# Conectors.net
KiCad netlist of a schematic drawn in Altium Designer
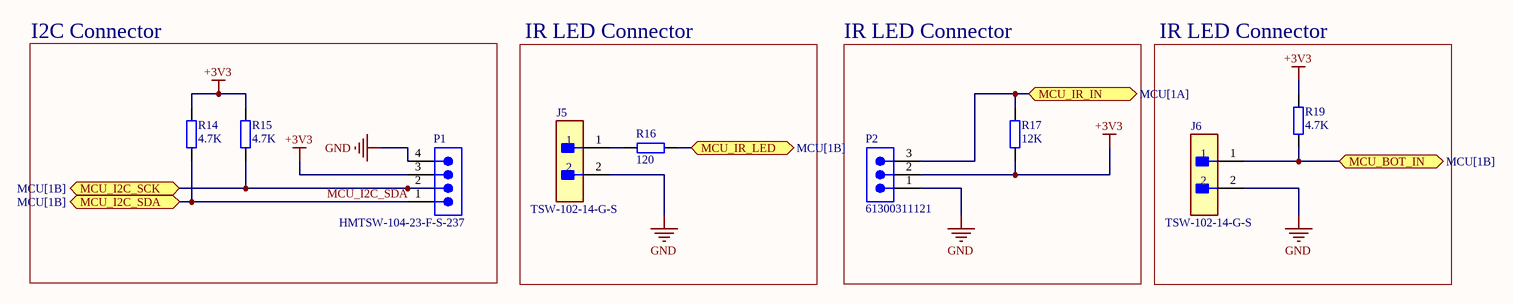
[diagram p0: Conectors.SchDoc]

(export (version "E")
  (design (tool "Eeschema 10.0.6"))
  (components
    (comp (ref "J5")
      (value "TSW-102-14-G-S")
      (footprint "FP-TSW-102-14-G-S-MFG")
      (description "CONN HEADER VERT 2POS 2.54MM")
      (libsource (lib "Altium Content Vault") (part "88c1139f9d239099ffebecbe3f7647a"))
    )
    (comp (ref "J6")
      (value "TSW-102-14-G-S")
      (footprint "FP-TSW-102-14-G-S-MFG")
      (description "CONN HEADER VERT 2POS 2.54MM")
      (libsource (lib "Altium Content Vault") (part "88c1139f9d239099ffebecbe3f7647a"))
    )
    (comp (ref "P1")
      (value "HMTSW-104-23-F-S-237")
      (footprint "SMTC-HMTSW-104-23-X-S-237")
      (fields (field (name "MANUFACTURER") "Samtec"))
      (libsource (lib "Altium Content Vault") (part "SMTC-HMTSW-104-23-X-S-237"))
    )
    (comp (ref "P2")
      (value "61300311121")
      (footprint "61300311121")
      (libsource (lib "Altium Content Vault") (part "Header_Male_1R_03P"))
    )
    (comp (ref "R14")
      (value "4.7K")
      (footprint "RES_0603")
      (description "Resistor SMD 0603")
      (libsource (lib "Schematic-Lib-PhilsLab") (part "RES_0603"))
    )
    (comp (ref "R15")
      (value "4.7K")
      (footprint "RES_0603")
      (description "Resistor SMD 0603")
      (libsource (lib "Schematic-Lib-PhilsLab") (part "RES_0603"))
    )
    (comp (ref "R16")
      (value "120")
      (footprint "RES_0603")
      (description "Resistor SMD 0603")
      (libsource (lib "Schematic-Lib-PhilsLab") (part "RES_0603"))
    )
    (comp (ref "R17")
      (value "12K")
      (footprint "RES_0603")
      (description "Resistor SMD 0603")
      (libsource (lib "Schematic-Lib-PhilsLab") (part "RES_0603"))
    )
    (comp (ref "R19")
      (value "4.7K")
      (footprint "RES_0603")
      (description "Resistor SMD 0603")
      (libsource (lib "Schematic-Lib-PhilsLab") (part "RES_0603"))
    )
  )
  (nets
    (net (code "1") (name "+3V3") (class "Default")
      (node (ref "P1") (pin "3") (pinfunction "3_3") (pintype "passive"))
      (node (ref "P2") (pin "2") (pinfunction "2_2") (pintype "passive"))
      (node (ref "R14") (pin "2") (pinfunction "2_2") (pintype "passive"))
      (node (ref "R15") (pin "2") (pinfunction "2_2") (pintype "passive"))
      (node (ref "R17") (pin "1") (pinfunction "1_1") (pintype "passive"))
      (node (ref "R19") (pin "1") (pinfunction "1_1") (pintype "passive"))
    )
    (net (code "2") (name "/MCU_BOT_IN") (class "Default")
      (node (ref "J6") (pin "1") (pinfunction "1_1") (pintype "passive"))
      (node (ref "R19") (pin "2") (pinfunction "2_2") (pintype "passive"))
    )
    (net (code "3") (name "/MCU_I2C_SCK") (class "Default")
      (node (ref "P1") (pin "2") (pinfunction "2_2") (pintype "passive"))
      (node (ref "R15") (pin "1") (pinfunction "1_1") (pintype "passive"))
    )
    (net (code "4") (name "/MCU_I2C_SDA") (class "Default")
      (node (ref "P1") (pin "1") (pinfunction "1_1") (pintype "passive"))
      (node (ref "R14") (pin "1") (pinfunction "1_1") (pintype "passive"))
    )
    (net (code "5") (name "/MCU_IR_IN") (class "Default")
      (node (ref "P2") (pin "3") (pinfunction "3_3") (pintype "passive"))
      (node (ref "R17") (pin "2") (pinfunction "2_2") (pintype "passive"))
    )
    (net (code "6") (name "/MCU_IR_LED") (class "Default")
      (node (ref "R16") (pin "1") (pinfunction "1_1") (pintype "passive"))
    )
    (net (code "7") (name "GND") (class "Default")
      (node (ref "J5") (pin "2") (pinfunction "2_2") (pintype "passive"))
      (node (ref "J6") (pin "2") (pinfunction "2_2") (pintype "passive"))
      (node (ref "P1") (pin "4") (pinfunction "4_4") (pintype "passive"))
      (node (ref "P2") (pin "1") (pinfunction "1_1") (pintype "passive"))
    )
    (net (code "8") (name "Net-(J5-Pad1)") (class "Default")
      (node (ref "J5") (pin "1") (pinfunction "1_1") (pintype "passive"))
      (node (ref "R16") (pin "2") (pinfunction "2_2") (pintype "passive"))
    )
  )
)
